# nRF24L01-Chip-v13.net
KiCad netlist of a schematic drawn in EAGLE
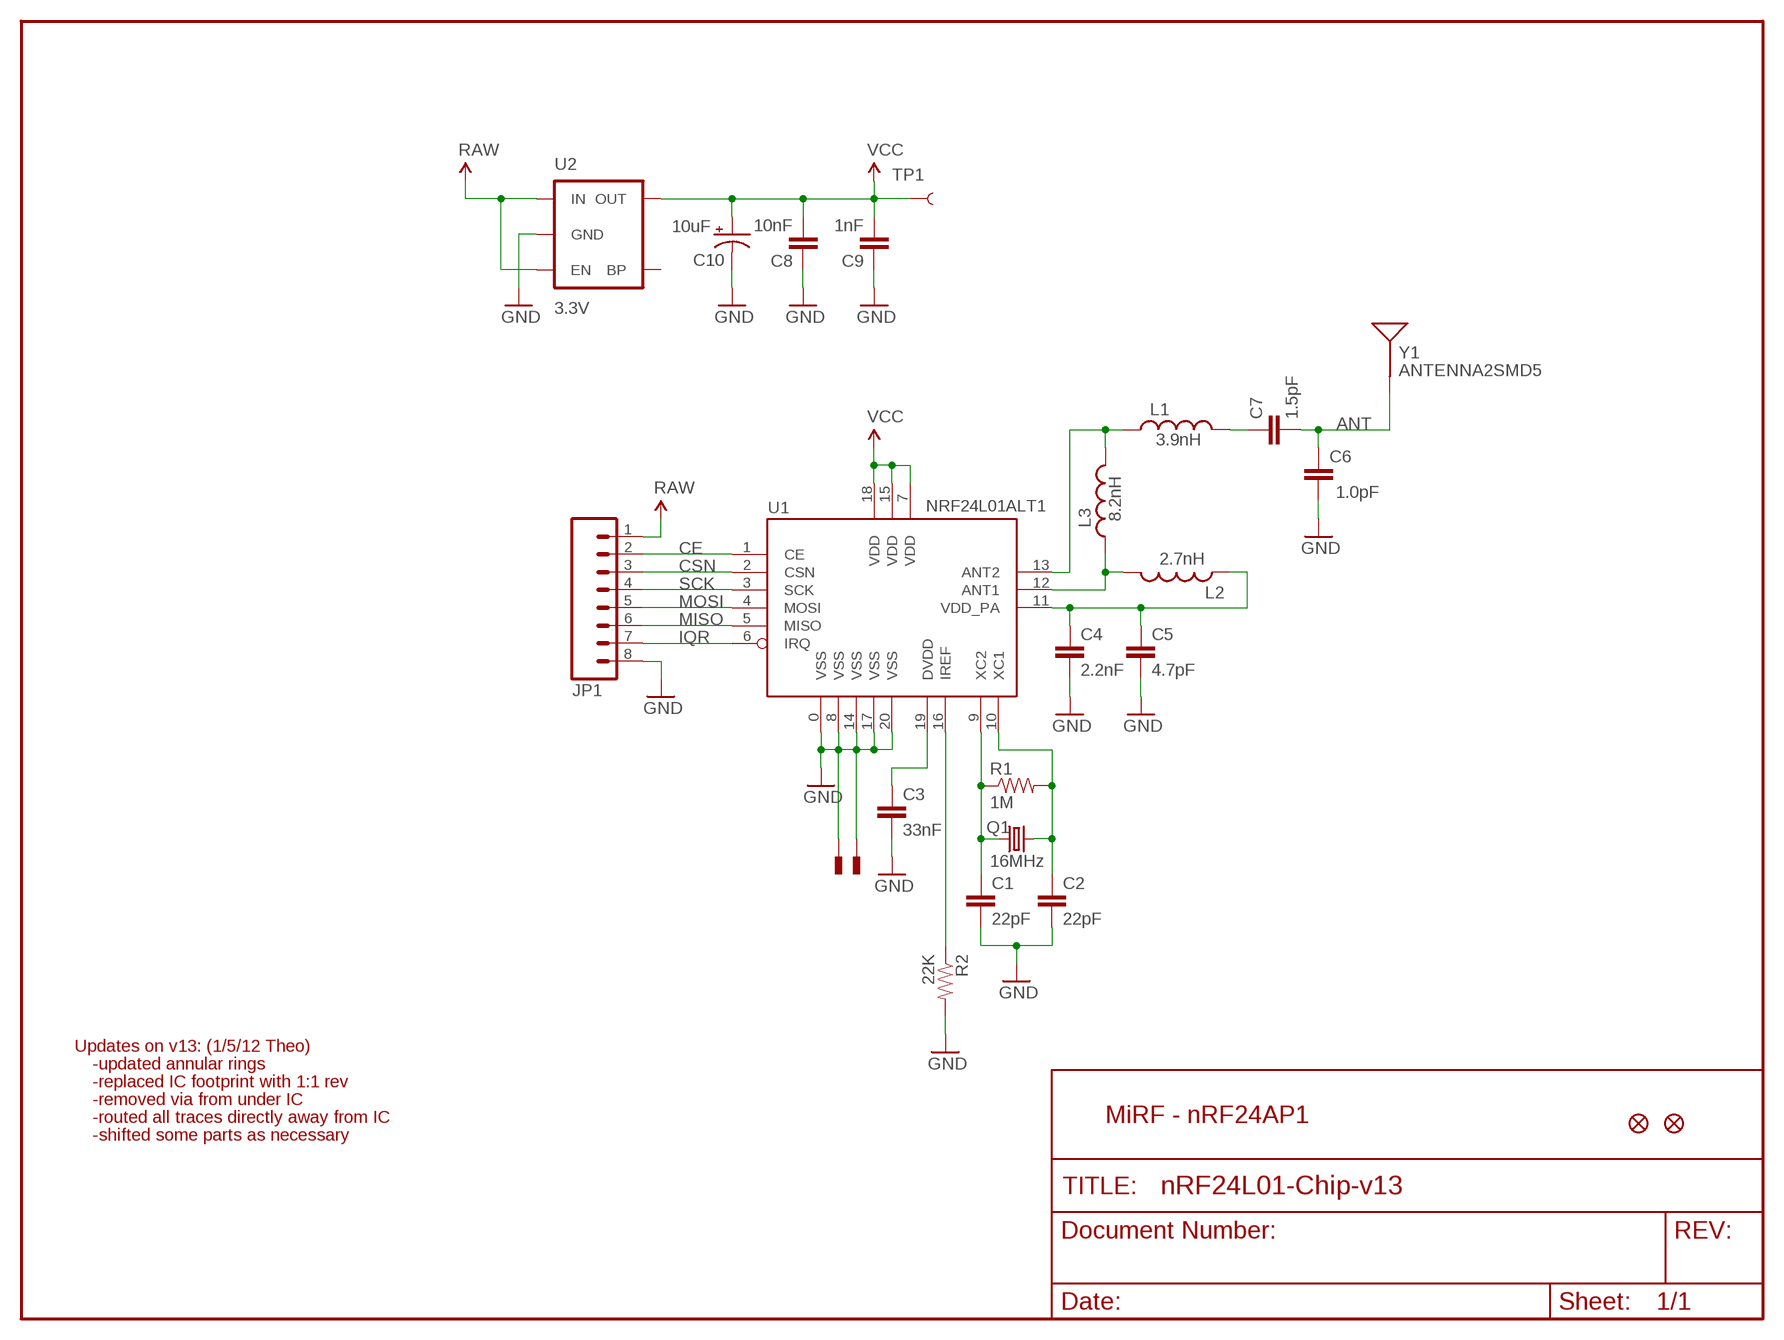
[diagram p0: schematic, sheet 1]

(export (version "E")
  (design (tool "Eeschema 10.0.6"))
  (components
    (comp (ref "C1")
      (value "22pF")
      (footprint "eagle-import:0402-CAP")
      (libsource (lib "eagle-import") (part "CAP0402-CAP"))
    )
    (comp (ref "C2")
      (value "22pF")
      (footprint "eagle-import:0402-CAP")
      (libsource (lib "eagle-import") (part "CAP0402-CAP"))
    )
    (comp (ref "C3")
      (value "33nF")
      (footprint "eagle-import:0402-CAP")
      (libsource (lib "eagle-import") (part "CAP0402-CAP"))
    )
    (comp (ref "C4")
      (value "2.2nF")
      (footprint "eagle-import:0402-CAP")
      (libsource (lib "eagle-import") (part "CAP0402-CAP"))
    )
    (comp (ref "C5")
      (value "4.7pF")
      (footprint "eagle-import:0402-CAP")
      (libsource (lib "eagle-import") (part "CAP0402-CAP"))
    )
    (comp (ref "C6")
      (value "1.0pF")
      (footprint "eagle-import:0402-CAP")
      (libsource (lib "eagle-import") (part "CAP0402-CAP"))
    )
    (comp (ref "C7")
      (value "1.5pF")
      (footprint "eagle-import:0402-CAP")
      (libsource (lib "eagle-import") (part "CAP0402-CAP"))
    )
    (comp (ref "C8")
      (value "10nF")
      (footprint "eagle-import:0402-CAP")
      (libsource (lib "eagle-import") (part "CAP0402-CAP"))
    )
    (comp (ref "C9")
      (value "1nF")
      (footprint "eagle-import:0402-CAP")
      (libsource (lib "eagle-import") (part "CAP0402-CAP"))
    )
    (comp (ref "C10")
      (value "10uF")
      (footprint "eagle-import:EIA3216")
      (libsource (lib "eagle-import") (part "CAP_POL1206"))
    )
    (comp (ref "JP1")
      (value "M081X08")
      (footprint "eagle-import:1X08")
      (libsource (lib "eagle-import") (part "M081X08"))
    )
    (comp (ref "JP2")
      (value "FIDUCIALUFIDUCIAL")
      (footprint "eagle-import:MICRO-FIDUCIAL")
      (libsource (lib "eagle-import") (part "FIDUCIALUFIDUCIAL"))
    )
    (comp (ref "JP3")
      (value "FIDUCIALUFIDUCIAL")
      (footprint "eagle-import:MICRO-FIDUCIAL")
      (libsource (lib "eagle-import") (part "FIDUCIALUFIDUCIAL"))
    )
    (comp (ref "L1")
      (value "3.9nH")
      (footprint "eagle-import:C0402")
      (libsource (lib "eagle-import") (part "INDUCTOR0402"))
    )
    (comp (ref "L2")
      (value "2.7nH")
      (footprint "eagle-import:C0402")
      (libsource (lib "eagle-import") (part "INDUCTOR0402"))
    )
    (comp (ref "L3")
      (value "8.2nH")
      (footprint "eagle-import:C0402")
      (libsource (lib "eagle-import") (part "INDUCTOR0402"))
    )
    (comp (ref "Q1")
      (value "16MHz")
      (footprint "eagle-import:CRYSTAL-SMD-5X3")
      (libsource (lib "eagle-import") (part "CRYSTAL5X3"))
    )
    (comp (ref "R1")
      (value "1M")
      (footprint "eagle-import:0402-RES")
      (libsource (lib "eagle-import") (part "RESISTOR0402-RES"))
    )
    (comp (ref "R2")
      (value "22K")
      (footprint "eagle-import:0402-RES")
      (libsource (lib "eagle-import") (part "RESISTOR0402-RES"))
    )
    (comp (ref "TP1")
      (value "TEST-POINT3X5")
      (footprint "eagle-import:PAD.03X.05")
      (libsource (lib "eagle-import") (part "TEST-POINT3X5"))
    )
    (comp (ref "U$1")
      (value "PAD")
      (footprint "eagle-import:PAD-0.008")
      (libsource (lib "eagle-import") (part "PAD"))
    )
    (comp (ref "U$4")
      (value "PAD")
      (footprint "eagle-import:PAD-0.008")
      (libsource (lib "eagle-import") (part "PAD"))
    )
    (comp (ref "U1")
      (value "NRF24L01ALT1")
      (footprint "eagle-import:QFN20_ALT1")
      (libsource (lib "eagle-import") (part "NRF24L01ALT1"))
    )
    (comp (ref "U2")
      (value "3.3V")
      (footprint "eagle-import:SOT23-5")
      (libsource (lib "eagle-import") (part "V_REG_LDOSMD"))
    )
    (comp (ref "Y1")
      (value "ANTENNA2SMD5")
      (footprint "eagle-import:ANTENNA-CHIP5")
      (libsource (lib "eagle-import") (part "ANTENNA2SMD5"))
    )
  )
  (nets
    (net (code "1") (name "/ANT") (class "Default")
      (node (ref "C6") (pin "2") (pinfunction "2_2") (pintype "passive"))
      (node (ref "C7") (pin "2") (pinfunction "2_2") (pintype "passive"))
      (node (ref "Y1") (pin "FEED") (pinfunction "SIGNAL_FEED") (pintype "bidirectional"))
    )
    (net (code "2") (name "/CE") (class "Default")
      (node (ref "JP1") (pin "2") (pinfunction "2_2") (pintype "passive"))
      (node (ref "U1") (pin "1") (pinfunction "CE_1") (pintype "input"))
    )
    (net (code "3") (name "/CSN") (class "Default")
      (node (ref "JP1") (pin "3") (pinfunction "3_3") (pintype "passive"))
      (node (ref "U1") (pin "2") (pinfunction "CSN_2") (pintype "input"))
    )
    (net (code "4") (name "/IQR") (class "Default")
      (node (ref "JP1") (pin "7") (pinfunction "7_7") (pintype "passive"))
      (node (ref "U1") (pin "6") (pinfunction "IRQ_6") (pintype "output"))
    )
    (net (code "5") (name "/MISO") (class "Default")
      (node (ref "JP1") (pin "6") (pinfunction "6_6") (pintype "passive"))
      (node (ref "U1") (pin "5") (pinfunction "MISO_5") (pintype "output"))
    )
    (net (code "6") (name "/MOSI") (class "Default")
      (node (ref "JP1") (pin "5") (pinfunction "5_5") (pintype "passive"))
      (node (ref "U1") (pin "4") (pinfunction "MOSI_4") (pintype "input"))
    )
    (net (code "7") (name "/SCK") (class "Default")
      (node (ref "JP1") (pin "4") (pinfunction "4_4") (pintype "passive"))
      (node (ref "U1") (pin "3") (pinfunction "SCK_3") (pintype "input"))
    )
    (net (code "8") (name "GND") (class "Default")
      (node (ref "C1") (pin "2") (pinfunction "2_2") (pintype "passive"))
      (node (ref "C10") (pin "C") (pinfunction "-_C") (pintype "passive"))
      (node (ref "C2") (pin "2") (pinfunction "2_2") (pintype "passive"))
      (node (ref "C3") (pin "2") (pinfunction "2_2") (pintype "passive"))
      (node (ref "C4") (pin "2") (pinfunction "2_2") (pintype "passive"))
      (node (ref "C5") (pin "2") (pinfunction "2_2") (pintype "passive"))
      (node (ref "C6") (pin "1") (pinfunction "1_1") (pintype "passive"))
      (node (ref "C8") (pin "1") (pinfunction "1_1") (pintype "passive"))
      (node (ref "C9") (pin "1") (pinfunction "1_1") (pintype "passive"))
      (node (ref "JP1") (pin "8") (pinfunction "8_8") (pintype "passive"))
      (node (ref "R2") (pin "2") (pinfunction "2_2") (pintype "passive"))
      (node (ref "U$1") (pin "P$1") (pinfunction "P$1_P$1") (pintype "bidirectional"))
      (node (ref "U$4") (pin "P$1") (pinfunction "P$1_P$1") (pintype "bidirectional"))
      (node (ref "U1") (pin "0") (pinfunction "VSS_0") (pintype "power_in"))
      (node (ref "U1") (pin "14") (pinfunction "VSS_14") (pintype "power_in"))
      (node (ref "U1") (pin "17") (pinfunction "VSS_17") (pintype "power_in"))
      (node (ref "U1") (pin "20") (pinfunction "VSS_20") (pintype "power_in"))
      (node (ref "U1") (pin "8") (pinfunction "VSS_8") (pintype "power_in"))
      (node (ref "U2") (pin "2") (pinfunction "GND_2") (pintype "input"))
    )
    (net (code "9") (name "Net-(C7-Pad1)") (class "Default")
      (node (ref "C7") (pin "1") (pinfunction "1_1") (pintype "passive"))
      (node (ref "L1") (pin "2") (pinfunction "2_2") (pintype "passive"))
    )
    (net (code "10") (name "Net-(Q1-2)") (class "Default")
      (node (ref "C2") (pin "1") (pinfunction "1_1") (pintype "passive"))
      (node (ref "Q1") (pin "3") (pinfunction "2_3") (pintype "passive"))
      (node (ref "R1") (pin "2") (pinfunction "2_2") (pintype "passive"))
      (node (ref "U1") (pin "10") (pinfunction "XC1_10") (pintype "input"))
    )
    (net (code "11") (name "Net-(U1-ANT1)") (class "Default")
      (node (ref "L2") (pin "2") (pinfunction "2_2") (pintype "passive"))
      (node (ref "L3") (pin "1") (pinfunction "1_1") (pintype "passive"))
      (node (ref "U1") (pin "12") (pinfunction "ANT1_12") (pintype "output"))
    )
    (net (code "12") (name "Net-(U1-ANT2)") (class "Default")
      (node (ref "L1") (pin "1") (pinfunction "1_1") (pintype "passive"))
      (node (ref "L3") (pin "2") (pinfunction "2_2") (pintype "passive"))
      (node (ref "U1") (pin "13") (pinfunction "ANT2_13") (pintype "output"))
    )
    (net (code "13") (name "Net-(U1-DVDD)") (class "Default")
      (node (ref "C3") (pin "1") (pinfunction "1_1") (pintype "passive"))
      (node (ref "U1") (pin "19") (pinfunction "DVDD_19") (pintype "power_in"))
    )
    (net (code "14") (name "Net-(U1-IREF)") (class "Default")
      (node (ref "R2") (pin "1") (pinfunction "1_1") (pintype "passive"))
      (node (ref "U1") (pin "16") (pinfunction "IREF_16") (pintype "input"))
    )
    (net (code "15") (name "Net-(U1-VDD_PA)") (class "Default")
      (node (ref "C4") (pin "1") (pinfunction "1_1") (pintype "passive"))
      (node (ref "C5") (pin "1") (pinfunction "1_1") (pintype "passive"))
      (node (ref "L2") (pin "1") (pinfunction "1_1") (pintype "passive"))
      (node (ref "U1") (pin "11") (pinfunction "VDD_PA_11") (pintype "power_in"))
    )
    (net (code "16") (name "Net-(U1-XC2)") (class "Default")
      (node (ref "C1") (pin "1") (pinfunction "1_1") (pintype "passive"))
      (node (ref "Q1") (pin "1") (pinfunction "1_1") (pintype "passive"))
      (node (ref "R1") (pin "1") (pinfunction "1_1") (pintype "passive"))
      (node (ref "U1") (pin "9") (pinfunction "XC2_9") (pintype "input"))
    )
    (net (code "17") (name "RAW") (class "Default")
      (node (ref "JP1") (pin "1") (pinfunction "1_1") (pintype "passive"))
      (node (ref "U2") (pin "1") (pinfunction "IN_1") (pintype "input"))
      (node (ref "U2") (pin "3") (pinfunction "EN_3") (pintype "input"))
    )
    (net (code "18") (name "VCC") (class "Default")
      (node (ref "C10") (pin "A") (pinfunction "+_A") (pintype "passive"))
      (node (ref "C8") (pin "2") (pinfunction "2_2") (pintype "passive"))
      (node (ref "C9") (pin "2") (pinfunction "2_2") (pintype "passive"))
      (node (ref "TP1") (pin "P$1") (pinfunction "1_P$1") (pintype "bidirectional"))
      (node (ref "U1") (pin "15") (pinfunction "VDD_15") (pintype "power_in"))
      (node (ref "U1") (pin "18") (pinfunction "VDD_18") (pintype "power_in"))
      (node (ref "U1") (pin "7") (pinfunction "VDD_7") (pintype "power_in"))
      (node (ref "U2") (pin "5") (pinfunction "OUT_5") (pintype "passive"))
    )
    (net (code "19") (name "unconnected-(U2-BP-Pad4)") (class "Default")
      (node (ref "U2") (pin "4") (pinfunction "BP_4") (pintype "input"))
    )
  )
)
